# SCH_WINGLET_BMU.net
KiCad netlist of a schematic drawn in Altium Designer
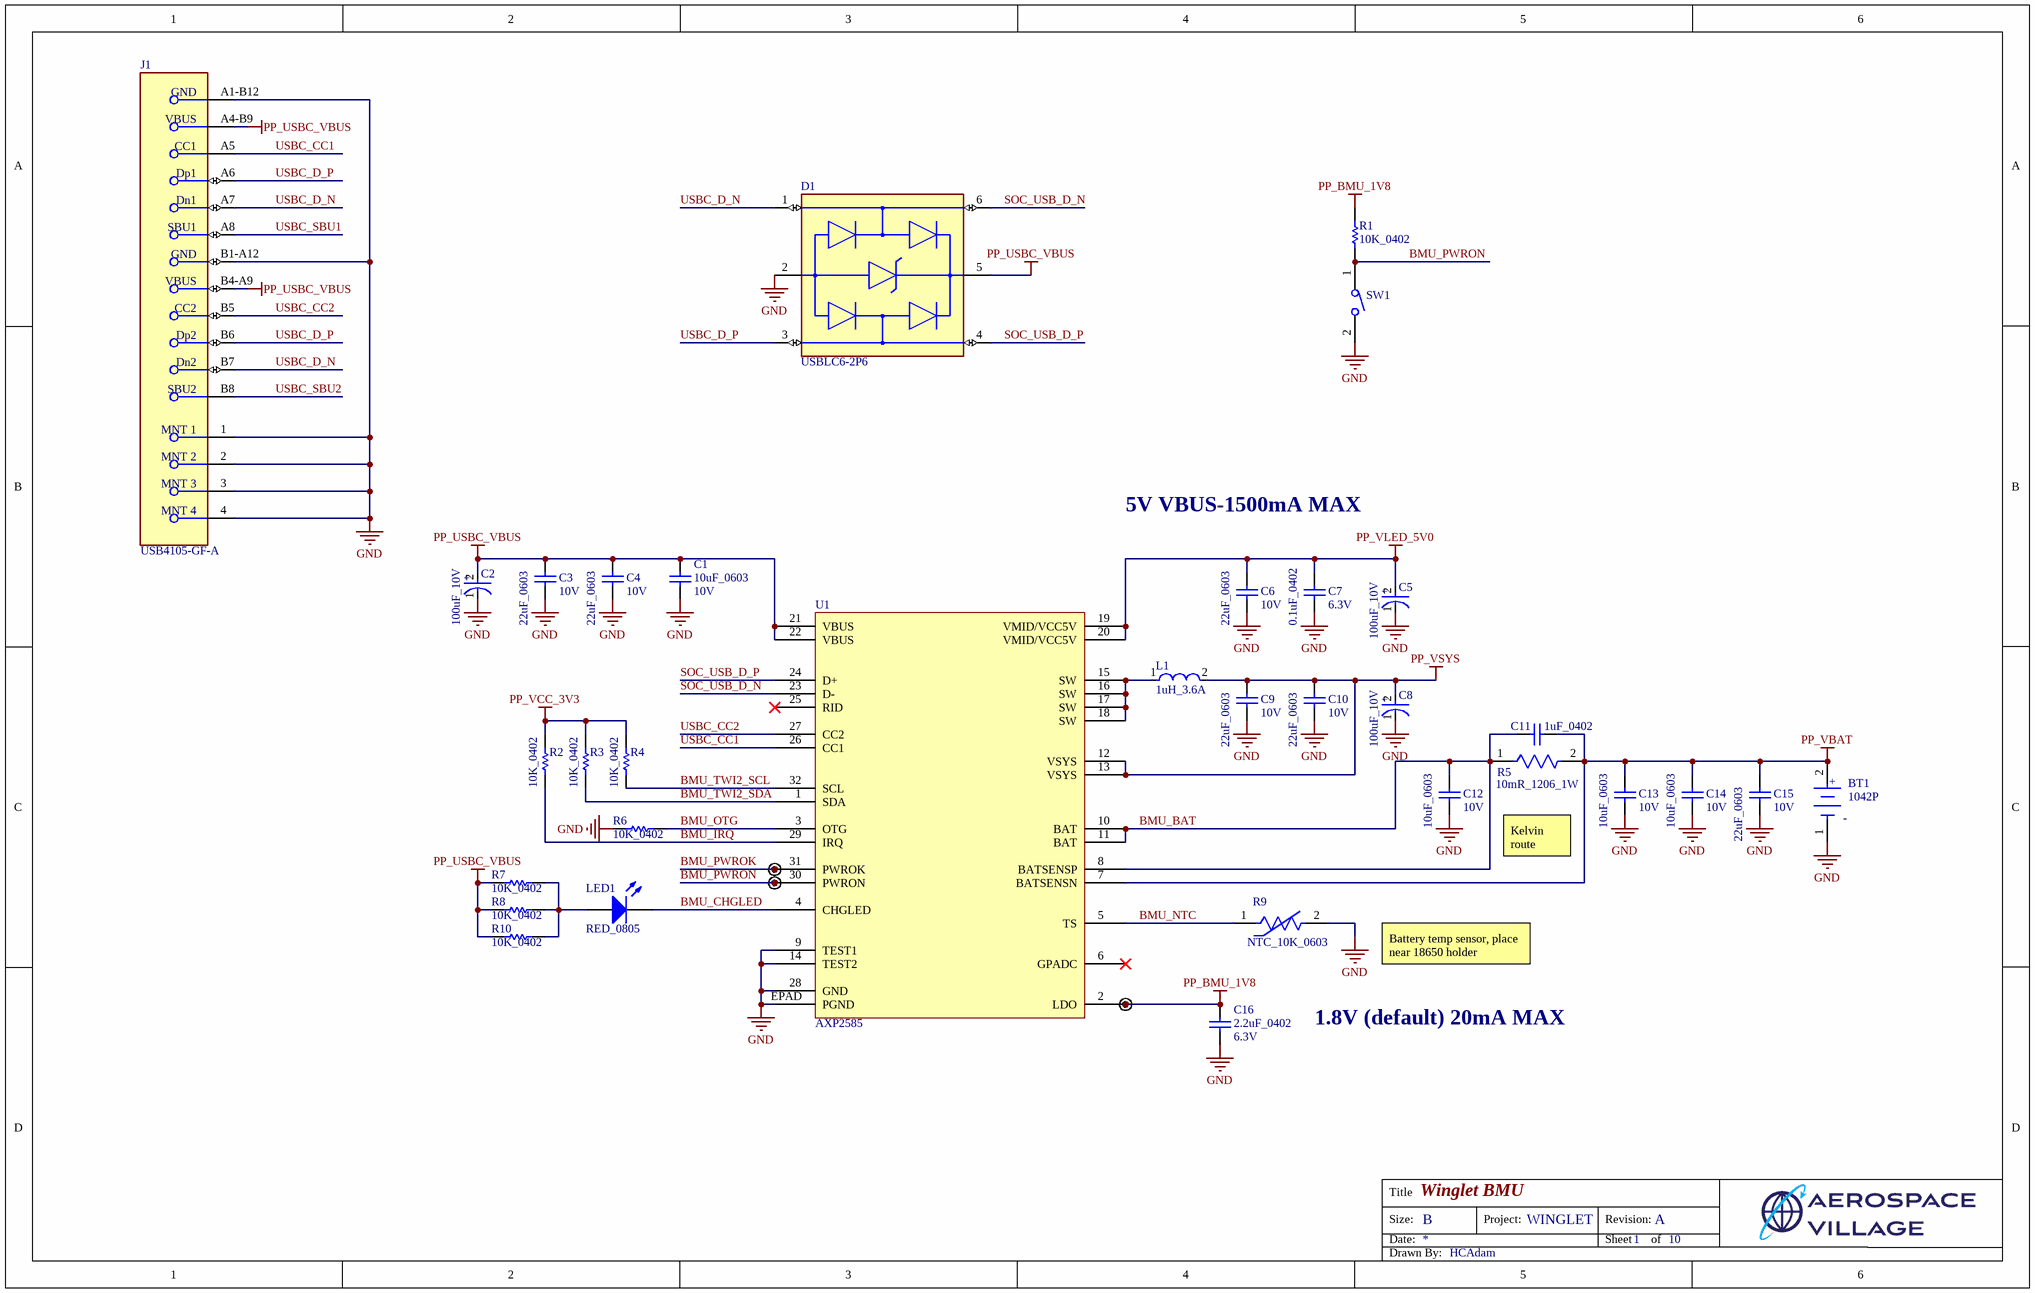
[diagram p0: SCH_WINGLET_BMU.SchDoc]

(export (version "E")
  (design (tool "Eeschema 10.0.6"))
  (components
    (comp (ref "BT1")
      (value "1042P")
      (footprint "FP-1042P-MFG")
      (description "BATTERY HOLDER 18650 SMD TAB")
      (libsource (lib "Altium Content Vault") (part "60d3b5b901a8747834971d0eb8cf3fd"))
    )
    (comp (ref "C1")
      (value "10uF_0603")
      (footprint "CAPC1609X100X15NL20")
      (fields
        (field (name "PART NUMBER") "TACL106M006XTA")
        (field (name "MANUFACTURER") "AVX Interconnect / Elco")
        (field (name "VOLTAGE RATING") "10V")
      )
      (libsource (lib "Altium Content Vault") (part "CAP"))
    )
    (comp (ref "C2")
      (value "100uF_10V")
      (footprint "FP-TAJB-MFG")
      (description "100uF 10V ±10% 1.7Ω SMD CASE-B (3528) Tantalum Capacitor")
      (fields (field (name "VOLTAGE") "6.3V") (field (name "TOLERANCE") "10%"))
      (libsource (lib "Altium Content Vault") (part "203bc49f2ac43e59fd269a8c329ed05"))
    )
    (comp (ref "C3")
      (value "22uF_0603")
      (footprint "CAPC1608X100X20NL10")
      (fields
        (field (name "MANUFACTURER") "TDK")
        (field (name "TOLERANCE") "±20%")
        (field (name "PCN PART NUMBER") "MLCCPartNumberChange30/Nov/2012")
        (field (name "VOLTAGE RATING") "10V")
      )
      (libsource (lib "Altium Content Vault") (part "CAP-NP-2"))
    )
    (comp (ref "C4")
      (value "22uF_0603")
      (footprint "CAPC1608X100X20NL10")
      (fields
        (field (name "MANUFACTURER") "TDK")
        (field (name "TOLERANCE") "±20%")
        (field (name "PCN PART NUMBER") "MLCCPartNumberChange30/Nov/2012")
        (field (name "VOLTAGE RATING") "10V")
      )
      (libsource (lib "Altium Content Vault") (part "CAP-NP-2"))
    )
    (comp (ref "C5")
      (value "100uF_10V")
      (footprint "FP-TAJB-MFG")
      (description "100uF 10V ±10% 1.7Ω SMD CASE-B (3528) Tantalum Capacitor")
      (fields (field (name "VOLTAGE") "6.3V") (field (name "TOLERANCE") "10%"))
      (libsource (lib "Altium Content Vault") (part "203bc49f2ac43e59fd269a8c329ed05"))
    )
    (comp (ref "C6")
      (value "22uF_0603")
      (footprint "CAPC1608X100X20NL10")
      (fields
        (field (name "MANUFACTURER") "TDK")
        (field (name "TOLERANCE") "±20%")
        (field (name "PCN PART NUMBER") "MLCCPartNumberChange30/Nov/2012")
        (field (name "VOLTAGE RATING") "10V")
      )
      (libsource (lib "Altium Content Vault") (part "CAP-NP-2"))
    )
    (comp (ref "C7")
      (value "0.1uF_0402")
      (footprint "CAPC1005X56X25NL10T15")
      (description "04026D104KAT2A")
      (fields (field (name "MANUFACTURER") "AVX Interconnect / Elco") (field (name "VOLTAGE RATING") "6.3V"))
      (libsource (lib "Altium Content Vault") (part "CAP"))
    )
    (comp (ref "C8")
      (value "100uF_10V")
      (footprint "FP-TAJB-MFG")
      (description "100uF 10V ±10% 1.7Ω SMD CASE-B (3528) Tantalum Capacitor")
      (fields (field (name "VOLTAGE") "6.3V") (field (name "TOLERANCE") "10%"))
      (libsource (lib "Altium Content Vault") (part "203bc49f2ac43e59fd269a8c329ed05"))
    )
    (comp (ref "C9")
      (value "22uF_0603")
      (footprint "CAPC1608X100X20NL10")
      (fields
        (field (name "MANUFACTURER") "TDK")
        (field (name "TOLERANCE") "±20%")
        (field (name "PCN PART NUMBER") "MLCCPartNumberChange30/Nov/2012")
        (field (name "VOLTAGE RATING") "10V")
      )
      (libsource (lib "Altium Content Vault") (part "CAP-NP-2"))
    )
    (comp (ref "C10")
      (value "22uF_0603")
      (footprint "CAPC1608X100X20NL10")
      (fields
        (field (name "MANUFACTURER") "TDK")
        (field (name "TOLERANCE") "±20%")
        (field (name "PCN PART NUMBER") "MLCCPartNumberChange30/Nov/2012")
        (field (name "VOLTAGE RATING") "10V")
      )
      (libsource (lib "Altium Content Vault") (part "CAP-NP-2"))
    )
    (comp (ref "C11")
      (value "1uF_0402")
      (footprint "CAPC1005X55X25NL5T10")
      (fields (field (name "TOLERANCE") "10%") (field (name "PARTNUMBER") "GRM155R60J105KE19D"))
      (libsource (lib "Altium Content Vault") (part "CAP-NP-2"))
    )
    (comp (ref "C12")
      (value "10uF_0603")
      (footprint "CAPC1609X100X15NL20")
      (fields
        (field (name "PART NUMBER") "TACL106M006XTA")
        (field (name "MANUFACTURER") "AVX Interconnect / Elco")
        (field (name "VOLTAGE RATING") "10V")
      )
      (libsource (lib "Altium Content Vault") (part "CAP"))
    )
    (comp (ref "C13")
      (value "10uF_0603")
      (footprint "CAPC1609X100X15NL20")
      (fields
        (field (name "PART NUMBER") "TACL106M006XTA")
        (field (name "MANUFACTURER") "AVX Interconnect / Elco")
        (field (name "VOLTAGE RATING") "10V")
      )
      (libsource (lib "Altium Content Vault") (part "CAP"))
    )
    (comp (ref "C14")
      (value "10uF_0603")
      (footprint "CAPC1609X100X15NL20")
      (fields
        (field (name "PART NUMBER") "TACL106M006XTA")
        (field (name "MANUFACTURER") "AVX Interconnect / Elco")
        (field (name "VOLTAGE RATING") "10V")
      )
      (libsource (lib "Altium Content Vault") (part "CAP"))
    )
    (comp (ref "C15")
      (value "22uF_0603")
      (footprint "CAPC1608X100X20NL10")
      (fields
        (field (name "MANUFACTURER") "TDK")
        (field (name "TOLERANCE") "±20%")
        (field (name "PCN PART NUMBER") "MLCCPartNumberChange30/Nov/2012")
        (field (name "VOLTAGE RATING") "10V")
      )
      (libsource (lib "Altium Content Vault") (part "CAP-NP-2"))
    )
    (comp (ref "C16")
      (value "2.2uF_0402")
      (footprint "CAPC1005X55X25NL05T10")
      (description "GRM155R60J225ME15D")
      (fields (field (name "MANUFACTURER") "Murata") (field (name "VOLTAGE RATING") "6.3V"))
      (libsource (lib "Altium Content Vault") (part "CAP"))
    )
    (comp (ref "D1")
      (value "USBLC6-2P6")
      (footprint "FP-SOT-666-MFG")
      (description "TVS DIODE 5.25V 17V SOT666")
      (libsource (lib "Altium Content Vault") (part "c871e55f7e3243d341edbd671b98d92"))
    )
    (comp (ref "J1")
      (value "USB4105-GF-A")
      (footprint "FP-USB4105-GF-A-MFG")
      (description "CONN RCPT USB2.0 TYPEC 5A")
      (fields
        (field (name "MANUFACTURER") "GCT")
        (field (name "OCTOPART") "https://octopart.com/usb4105-gf-a-gct-106627878")
      )
      (libsource (lib "Altium Content Vault") (part "e7c17a616881a82b79941196b4bec10"))
    )
    (comp (ref "L1")
      (value "1uH_3.6A")
      (footprint "FP-NRS5020-MFG")
      (description "Shielded Wirewound Inductor 1uH 30% 3.71A 25.2mΩ SMD\r\nNRS5020T1R0NMGJ")
      (fields (field (name "TOLERANCE") "30%"))
      (libsource (lib "Altium Content Vault") (part "725321dda6339637d4d059423bc1c3c"))
    )
    (comp (ref "LED1")
      (value "RED_0805")
      (footprint "0805_A")
      (description "LED RED 0805")
      (fields (field (name "PARTNUMBER") "150080GS75000") (field (name "MANUFACTURER") "Wuerth Elektronik"))
      (libsource (lib "Altium Content Vault") (part "WE-LED_K1A2-2"))
    )
    (comp (ref "R1")
      (value "10K_0402")
      (footprint "RESC1005X40X25NL05T05")
      (fields (field (name "TOLERANCE") "1%") (field (name "MANUFACTURER") "Panasonic"))
      (libsource (lib "Altium Content Vault") (part "RES-2"))
    )
    (comp (ref "R2")
      (value "10K_0402")
      (footprint "RESC1005X40X25NL05T05")
      (fields (field (name "TOLERANCE") "1%") (field (name "MANUFACTURER") "Panasonic"))
      (libsource (lib "Altium Content Vault") (part "RES-2"))
    )
    (comp (ref "R3")
      (value "10K_0402")
      (footprint "RESC1005X40X25NL05T05")
      (fields (field (name "TOLERANCE") "1%") (field (name "MANUFACTURER") "Panasonic"))
      (libsource (lib "Altium Content Vault") (part "RES-2"))
    )
    (comp (ref "R4")
      (value "10K_0402")
      (footprint "RESC1005X40X25NL05T05")
      (fields (field (name "TOLERANCE") "1%") (field (name "MANUFACTURER") "Panasonic"))
      (libsource (lib "Altium Content Vault") (part "RES-2"))
    )
    (comp (ref "R5")
      (value "10mR_1206_1W")
      (footprint "FP-ERJ8BW-IPC_B")
      (description "RES 0.01 OHM 1% 1W 1206\r\nERJ-8BWFR010V")
      (fields (field (name "TOLERANCE") "1%"))
      (libsource (lib "Altium Content Vault") (part "1029c3af85768c4190bb7ad29bc67b5"))
    )
    (comp (ref "R6")
      (value "10K_0402")
      (footprint "RESC1005X40X25NL05T05")
      (fields (field (name "TOLERANCE") "1%") (field (name "MANUFACTURER") "Panasonic"))
      (libsource (lib "Altium Content Vault") (part "RES-2"))
    )
    (comp (ref "R7")
      (value "10K_0402")
      (footprint "RESC1005X40X25NL05T05")
      (fields (field (name "TOLERANCE") "1%") (field (name "MANUFACTURER") "Panasonic"))
      (libsource (lib "Altium Content Vault") (part "RES-2"))
    )
    (comp (ref "R8")
      (value "10K_0402")
      (footprint "RESC1005X40X25NL05T05")
      (fields (field (name "TOLERANCE") "1%") (field (name "MANUFACTURER") "Panasonic"))
      (libsource (lib "Altium Content Vault") (part "RES-2"))
    )
    (comp (ref "R9")
      (value "NTC_10K_0603")
      (footprint "FP-ERTJ1-IPC_C")
      (description "THERMISTOR NTC 10KOHM 3380K 0603\r\nERT-J1VG103JA")
      (fields (field (name "TOLERANCE") "5%"))
      (libsource (lib "Altium Content Vault") (part "3b148a6ebabc5fb4d708a66c052d352"))
    )
    (comp (ref "R10")
      (value "10K_0402")
      (footprint "RESC1005X40X25NL05T05")
      (fields (field (name "TOLERANCE") "1%") (field (name "MANUFACTURER") "Panasonic"))
      (libsource (lib "Altium Content Vault") (part "RES-2"))
    )
    (comp (ref "SW1")
      (value "GT-TC029B-H025-L1N")
      (footprint "LCSC_SMD_SW_SMALL")
      (description "SMD SPST Tactile Switch\r\nC843669")
      (libsource (lib "DCAV32_WINGLET_SCHLIB") (part "GT-TC029B-H025-L1N"))
    )
    (comp (ref "TP1")
      (value "TESTPOINT")
      (footprint "TESTPOINT-0.7MM-SINGLE-LAYER")
      (description "TESTPOINT SINGLE LAYER 0.7MM")
      (libsource (lib "DCAV32_WINGLET_SCHLIB") (part "TP_07"))
    )
    (comp (ref "TP2")
      (value "TESTPOINT")
      (footprint "TESTPOINT-0.7MM-SINGLE-LAYER")
      (description "TESTPOINT SINGLE LAYER 0.7MM")
      (libsource (lib "DCAV32_WINGLET_SCHLIB") (part "TP_07"))
    )
    (comp (ref "TP3")
      (value "TESTPOINT")
      (footprint "TESTPOINT-0.7MM-SINGLE-LAYER")
      (description "TESTPOINT SINGLE LAYER 0.7MM")
      (libsource (lib "DCAV32_WINGLET_SCHLIB") (part "TP_07"))
    )
    (comp (ref "U1")
      (value "AXP2585")
      (footprint "QFN127P600-8N")
      (description "AXP2585 Single Cell NVDC BMU with E-gauge")
      (libsource (lib "DCAV32_WINGLET_SCHLIB") (part "AXP2585"))
    )
  )
  (nets
    (net (code "1") (name "/BMU_BAT") (class "Default")
      (node (ref "C11") (pin "2") (pinfunction "2_2") (pintype "passive"))
      (node (ref "C12") (pin "2") (pinfunction "2_2") (pintype "passive"))
      (node (ref "R5") (pin "1") (pinfunction "1_1") (pintype "passive"))
      (node (ref "U1") (pin "10") (pinfunction "BAT_10") (pintype "passive"))
      (node (ref "U1") (pin "11") (pinfunction "BAT_11") (pintype "passive"))
      (node (ref "U1") (pin "8") (pinfunction "BATSENSP_8") (pintype "passive"))
    )
    (net (code "2") (name "/BMU_CHGLED") (class "Default")
      (node (ref "LED1") (pin "1") (pinfunction "K_1") (pintype "passive"))
      (node (ref "U1") (pin "4") (pinfunction "CHGLED_4") (pintype "passive"))
    )
    (net (code "3") (name "/BMU_IRQ") (class "Default")
      (node (ref "R2") (pin "2") (pinfunction "2_2") (pintype "passive"))
      (node (ref "U1") (pin "29") (pinfunction "IRQ_29") (pintype "passive"))
    )
    (net (code "4") (name "/BMU_NTC") (class "Default")
      (node (ref "R9") (pin "1") (pinfunction "1_1") (pintype "passive"))
      (node (ref "U1") (pin "5") (pinfunction "TS_5") (pintype "passive"))
    )
    (net (code "5") (name "/BMU_OTG") (class "Default")
      (node (ref "R6") (pin "2") (pinfunction "2_2") (pintype "passive"))
      (node (ref "U1") (pin "3") (pinfunction "OTG_3") (pintype "passive"))
    )
    (net (code "6") (name "/BMU_PWROK") (class "Default")
      (node (ref "TP1") (pin "1") (pinfunction "1_1") (pintype "passive"))
      (node (ref "U1") (pin "31") (pinfunction "PWROK_31") (pintype "passive"))
    )
    (net (code "7") (name "/BMU_PWRON") (class "Default")
      (node (ref "R1") (pin "2") (pinfunction "2_2") (pintype "passive"))
      (node (ref "SW1") (pin "1") (pintype "passive"))
      (node (ref "TP2") (pin "1") (pinfunction "1_1") (pintype "passive"))
      (node (ref "U1") (pin "30") (pinfunction "PWRON_30") (pintype "passive"))
    )
    (net (code "8") (name "/BMU_TWI2_SCL") (class "Default")
      (node (ref "R4") (pin "2") (pinfunction "2_2") (pintype "passive"))
      (node (ref "U1") (pin "32") (pinfunction "SCL_32") (pintype "passive"))
    )
    (net (code "9") (name "/BMU_TWI2_SDA") (class "Default")
      (node (ref "R3") (pin "2") (pinfunction "2_2") (pintype "passive"))
      (node (ref "U1") (pin "1") (pinfunction "SDA_1") (pintype "passive"))
    )
    (net (code "10") (name "/SOC_USB_D_N") (class "Default")
      (node (ref "D1") (pin "6") (pinfunction "I/O1_6") (pintype "bidirectional"))
      (node (ref "U1") (pin "23") (pinfunction "D-_23") (pintype "passive"))
    )
    (net (code "11") (name "/SOC_USB_D_P") (class "Default")
      (node (ref "D1") (pin "4") (pinfunction "I/O2_4") (pintype "bidirectional"))
      (node (ref "U1") (pin "24") (pinfunction "D+_24") (pintype "passive"))
    )
    (net (code "12") (name "/USBC_CC1") (class "Default")
      (node (ref "J1") (pin "A5") (pinfunction "CC1_A5") (pintype "power_in"))
      (node (ref "U1") (pin "26") (pinfunction "CC1_26") (pintype "passive"))
    )
    (net (code "13") (name "/USBC_CC2") (class "Default")
      (node (ref "J1") (pin "B5") (pinfunction "CC2_B5") (pintype "bidirectional"))
      (node (ref "U1") (pin "27") (pinfunction "CC2_27") (pintype "passive"))
    )
    (net (code "14") (name "/USBC_D_N") (class "Default")
      (node (ref "D1") (pin "1") (pinfunction "I/O1_1") (pintype "bidirectional"))
      (node (ref "J1") (pin "A7") (pinfunction "Dn1_A7") (pintype "bidirectional"))
      (node (ref "J1") (pin "B7") (pinfunction "Dn2_B7") (pintype "bidirectional"))
    )
    (net (code "15") (name "/USBC_D_P") (class "Default")
      (node (ref "D1") (pin "3") (pinfunction "I/O2_3") (pintype "bidirectional"))
      (node (ref "J1") (pin "A6") (pinfunction "Dp1_A6") (pintype "bidirectional"))
      (node (ref "J1") (pin "B6") (pinfunction "Dp2_B6") (pintype "bidirectional"))
    )
    (net (code "16") (name "/USBC_SBU1") (class "Default")
      (node (ref "J1") (pin "A8") (pinfunction "SBU1_A8") (pintype "bidirectional"))
    )
    (net (code "17") (name "/USBC_SBU2") (class "Default")
      (node (ref "J1") (pin "B8") (pinfunction "SBU2_B8") (pintype "power_in"))
    )
    (net (code "18") (name "GND") (class "Default")
      (node (ref "BT1") (pin "1") (pinfunction "C_1") (pintype "passive"))
      (node (ref "C1") (pin "1") (pinfunction "1_1") (pintype "passive"))
      (node (ref "C10") (pin "1") (pinfunction "1_1") (pintype "passive"))
      (node (ref "C12") (pin "1") (pinfunction "1_1") (pintype "passive"))
      (node (ref "C13") (pin "1") (pinfunction "1_1") (pintype "passive"))
      (node (ref "C14") (pin "1") (pinfunction "1_1") (pintype "passive"))
      (node (ref "C15") (pin "1") (pinfunction "1_1") (pintype "passive"))
      (node (ref "C16") (pin "1") (pinfunction "1_1") (pintype "passive"))
      (node (ref "C2") (pin "1") (pinfunction "C_1") (pintype "passive"))
      (node (ref "C3") (pin "1") (pinfunction "1_1") (pintype "passive"))
      (node (ref "C4") (pin "1") (pinfunction "1_1") (pintype "passive"))
      (node (ref "C5") (pin "1") (pinfunction "C_1") (pintype "passive"))
      (node (ref "C6") (pin "1") (pinfunction "1_1") (pintype "passive"))
      (node (ref "C7") (pin "1") (pinfunction "1_1") (pintype "passive"))
      (node (ref "C8") (pin "1") (pinfunction "C_1") (pintype "passive"))
      (node (ref "C9") (pin "1") (pinfunction "1_1") (pintype "passive"))
      (node (ref "D1") (pin "2") (pinfunction "GND_2") (pintype "power_in"))
      (node (ref "J1") (pin "1") (pinfunction "MNT_1_1") (pintype "power_in"))
      (node (ref "J1") (pin "2") (pinfunction "MNT_2_2") (pintype "power_in"))
      (node (ref "J1") (pin "3") (pinfunction "MNT_3_3") (pintype "power_in"))
      (node (ref "J1") (pin "4") (pinfunction "MNT_4_4") (pintype "power_in"))
      (node (ref "J1") (pin "A1-B12") (pinfunction "GND_A1-B12") (pintype "power_in"))
      (node (ref "J1") (pin "B1-A12") (pinfunction "GND_B1-A12") (pintype "bidirectional"))
      (node (ref "R6") (pin "1") (pinfunction "1_1") (pintype "passive"))
      (node (ref "R9") (pin "2") (pinfunction "2_2") (pintype "passive"))
      (node (ref "SW1") (pin "2") (pintype "passive"))
      (node (ref "U1") (pin "14") (pinfunction "TEST2_14") (pintype "passive"))
      (node (ref "U1") (pin "28") (pinfunction "GND_28") (pintype "passive"))
      (node (ref "U1") (pin "9") (pinfunction "TEST1_9") (pintype "passive"))
      (node (ref "U1") (pin "EPAD") (pinfunction "PGND_EPAD") (pintype "passive"))
    )
    (net (code "19") (name "Net-(L1-Pad1)") (class "Default")
      (node (ref "L1") (pin "1") (pinfunction "1_1") (pintype "passive"))
      (node (ref "U1") (pin "15") (pinfunction "SW_15") (pintype "passive"))
      (node (ref "U1") (pin "16") (pinfunction "SW_16") (pintype "passive"))
      (node (ref "U1") (pin "17") (pinfunction "SW_17") (pintype "passive"))
      (node (ref "U1") (pin "18") (pinfunction "SW_18") (pintype "passive"))
    )
    (net (code "20") (name "Net-(LED1-A)") (class "Default")
      (node (ref "LED1") (pin "2") (pinfunction "A_2") (pintype "passive"))
      (node (ref "R10") (pin "1") (pinfunction "1_1") (pintype "passive"))
      (node (ref "R7") (pin "1") (pinfunction "1_1") (pintype "passive"))
      (node (ref "R8") (pin "1") (pinfunction "1_1") (pintype "passive"))
    )
    (net (code "21") (name "PP_BMU_1V8") (class "Default")
      (node (ref "C16") (pin "2") (pinfunction "2_2") (pintype "passive"))
      (node (ref "R1") (pin "1") (pinfunction "1_1") (pintype "passive"))
      (node (ref "TP3") (pin "1") (pinfunction "1_1") (pintype "passive"))
      (node (ref "U1") (pin "2") (pinfunction "LDO_2") (pintype "passive"))
    )
    (net (code "22") (name "PP_USBC_VBUS") (class "Default")
      (node (ref "C1") (pin "2") (pinfunction "2_2") (pintype "passive"))
      (node (ref "C2") (pin "2") (pinfunction "A_2") (pintype "passive"))
      (node (ref "C3") (pin "2") (pinfunction "2_2") (pintype "passive"))
      (node (ref "C4") (pin "2") (pinfunction "2_2") (pintype "passive"))
      (node (ref "D1") (pin "5") (pinfunction "VBUS_5") (pintype "power_in"))
      (node (ref "J1") (pin "A4-B9") (pinfunction "VBUS_A4-B9") (pintype "power_in"))
      (node (ref "J1") (pin "B4-A9") (pinfunction "VBUS_B4-A9") (pintype "bidirectional"))
      (node (ref "R10") (pin "2") (pinfunction "2_2") (pintype "passive"))
      (node (ref "R7") (pin "2") (pinfunction "2_2") (pintype "passive"))
      (node (ref "R8") (pin "2") (pinfunction "2_2") (pintype "passive"))
      (node (ref "U1") (pin "21") (pinfunction "VBUS_21") (pintype "passive"))
      (node (ref "U1") (pin "22") (pinfunction "VBUS_22") (pintype "passive"))
    )
    (net (code "23") (name "PP_VBAT") (class "Default")
      (node (ref "BT1") (pin "2") (pinfunction "A_2") (pintype "passive"))
      (node (ref "C11") (pin "1") (pinfunction "1_1") (pintype "passive"))
      (node (ref "C13") (pin "2") (pinfunction "2_2") (pintype "passive"))
      (node (ref "C14") (pin "2") (pinfunction "2_2") (pintype "passive"))
      (node (ref "C15") (pin "2") (pinfunction "2_2") (pintype "passive"))
      (node (ref "R5") (pin "2") (pinfunction "2_2") (pintype "passive"))
      (node (ref "U1") (pin "7") (pinfunction "BATSENSN_7") (pintype "passive"))
    )
    (net (code "24") (name "PP_VCC_3V3") (class "Default")
      (node (ref "R2") (pin "1") (pinfunction "1_1") (pintype "passive"))
      (node (ref "R3") (pin "1") (pinfunction "1_1") (pintype "passive"))
      (node (ref "R4") (pin "1") (pinfunction "1_1") (pintype "passive"))
    )
    (net (code "25") (name "PP_VLED_5V0") (class "Default")
      (node (ref "C5") (pin "2") (pinfunction "A_2") (pintype "passive"))
      (node (ref "C6") (pin "2") (pinfunction "2_2") (pintype "passive"))
      (node (ref "C7") (pin "2") (pinfunction "2_2") (pintype "passive"))
      (node (ref "U1") (pin "19") (pinfunction "VMID/VCC5V_19") (pintype "passive"))
      (node (ref "U1") (pin "20") (pinfunction "VMID/VCC5V_20") (pintype "passive"))
    )
    (net (code "26") (name "PP_VSYS") (class "Default")
      (node (ref "C10") (pin "2") (pinfunction "2_2") (pintype "passive"))
      (node (ref "C8") (pin "2") (pinfunction "A_2") (pintype "passive"))
      (node (ref "C9") (pin "2") (pinfunction "2_2") (pintype "passive"))
      (node (ref "L1") (pin "2") (pinfunction "2_2") (pintype "passive"))
      (node (ref "U1") (pin "12") (pinfunction "VSYS_12") (pintype "passive"))
      (node (ref "U1") (pin "13") (pinfunction "VSYS_13") (pintype "passive"))
    )
    (net (code "27") (name "unconnected-(U1-GPADC-Pad6)") (class "Default")
      (node (ref "U1") (pin "6") (pinfunction "GPADC_6") (pintype "passive+no_connect"))
    )
    (net (code "28") (name "unconnected-(U1-RID-Pad25)") (class "Default")
      (node (ref "U1") (pin "25") (pinfunction "RID_25") (pintype "passive+no_connect"))
    )
  )
)
